# arduino_328p.net
KiCad netlist of a schematic drawn in EAGLE
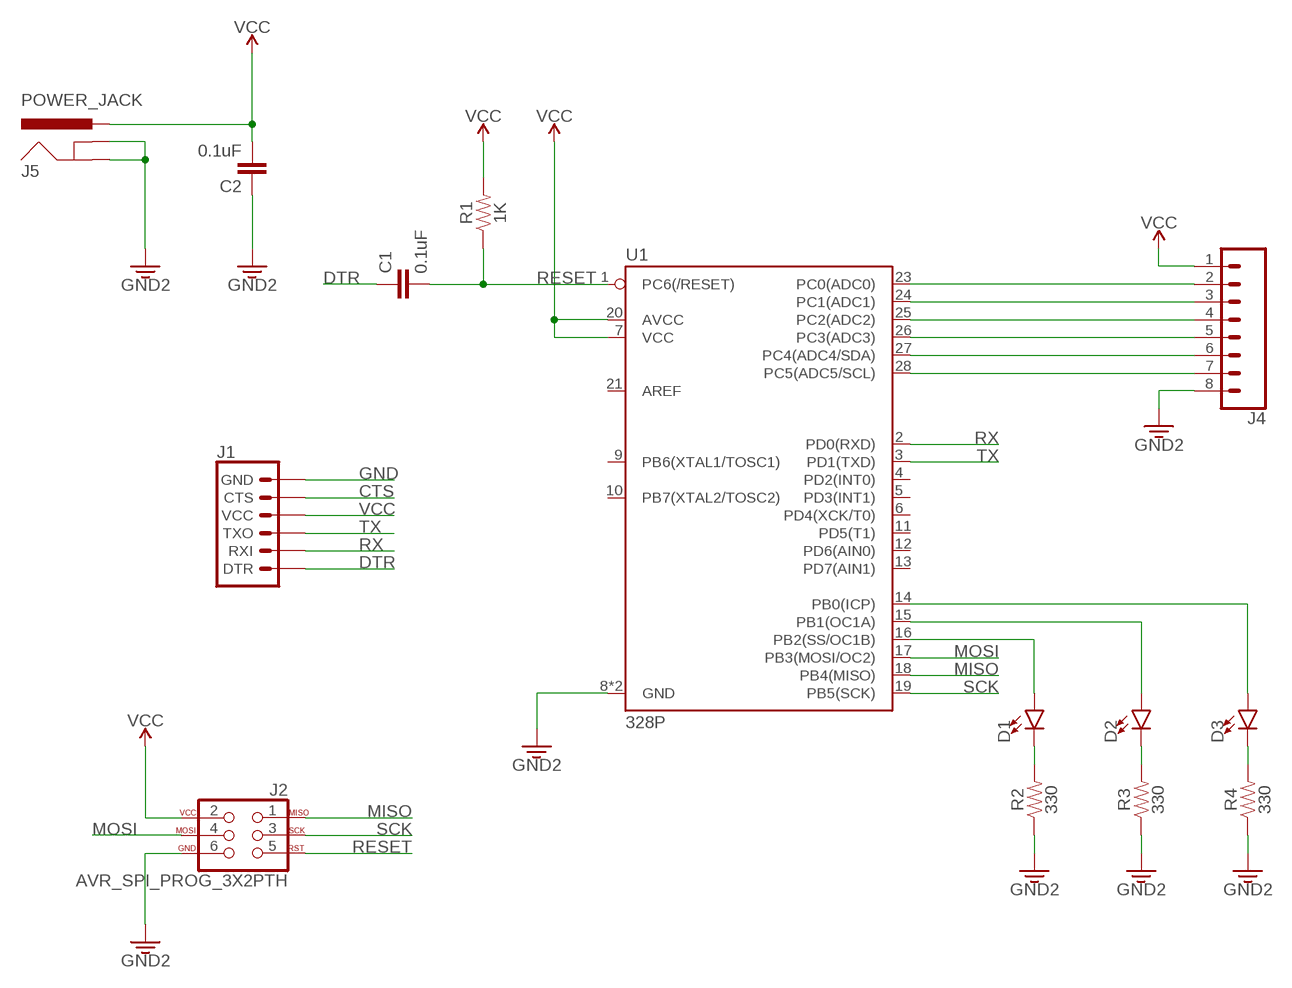
[diagram p0: schematic, sheet 1]

(export (version "E")
  (design (tool "Eeschema 10.0.6"))
  (components
    (comp (ref "C1")
      (value "0.1uF")
      (footprint "eagle-import:0402")
      (libsource (lib "eagle-import") (part "0.1UF-0402-6.3V-10%-X7R"))
    )
    (comp (ref "C2")
      (value "0.1uF")
      (footprint "eagle-import:0402")
      (libsource (lib "eagle-import") (part "0.1UF-0402-6.3V-10%-X7R"))
    )
    (comp (ref "D1")
      (value "LED1206")
      (footprint "eagle-import:LED-1206")
      (libsource (lib "eagle-import") (part "LED1206"))
    )
    (comp (ref "D2")
      (value "LED1206")
      (footprint "eagle-import:LED-1206")
      (libsource (lib "eagle-import") (part "LED1206"))
    )
    (comp (ref "D3")
      (value "LED1206")
      (footprint "eagle-import:LED-1206")
      (libsource (lib "eagle-import") (part "LED1206"))
    )
    (comp (ref "J1")
      (value "6_PIN_SERIAL_TARGETPTH-KIT")
      (footprint "eagle-import:1X06-KIT")
      (libsource (lib "eagle-import") (part "6_PIN_SERIAL_TARGETPTH-KIT"))
    )
    (comp (ref "J2")
      (value "AVR_SPI_PROG_3X2PTH")
      (footprint "eagle-import:2X3")
      (libsource (lib "eagle-import") (part "AVR_SPI_PROG_3X2PTH"))
    )
    (comp (ref "J4")
      (value "CONN_08\"")
      (footprint "eagle-import:1X08")
      (libsource (lib "eagle-import") (part "CONN_08{dblquote}"))
    )
    (comp (ref "J5")
      (value "POWER_JACK")
      (footprint "eagle-import:POWER_JACK_PTH")
      (libsource (lib "eagle-import") (part "POWER_JACK"))
    )
    (comp (ref "R1")
      (value "1K")
      (footprint "eagle-import:0805")
      (libsource (lib "eagle-import") (part "0.22OHM-0805-1/4W-1%"))
    )
    (comp (ref "R2")
      (value "330")
      (footprint "eagle-import:0805")
      (libsource (lib "eagle-import") (part "0.22OHM-0805-1/4W-1%"))
    )
    (comp (ref "R3")
      (value "330")
      (footprint "eagle-import:0805")
      (libsource (lib "eagle-import") (part "0.22OHM-0805-1/4W-1%"))
    )
    (comp (ref "R4")
      (value "330")
      (footprint "eagle-import:0805")
      (libsource (lib "eagle-import") (part "0.22OHM-0805-1/4W-1%"))
    )
    (comp (ref "U1")
      (value "328P")
      (footprint "eagle-import:DIP28")
      (libsource (lib "eagle-import") (part "ATMEGA328P_PDIP"))
    )
  )
  (nets
    (net (code "1") (name "/CTS") (class "Default")
      (node (ref "J1") (pin "5") (pinfunction "CTS_5") (pintype "passive"))
    )
    (net (code "2") (name "/DTR") (class "Default")
      (node (ref "C1") (pin "1") (pinfunction "1_1") (pintype "passive"))
      (node (ref "J1") (pin "1") (pinfunction "DTR_1") (pintype "passive"))
    )
    (net (code "3") (name "/MISO") (class "Default")
      (node (ref "J2") (pin "1") (pinfunction "1_1") (pintype "passive"))
      (node (ref "U1") (pin "18") (pinfunction "PB4(MISO)_18") (pintype "bidirectional"))
    )
    (net (code "4") (name "/MOSI") (class "Default")
      (node (ref "J2") (pin "4") (pinfunction "4_4") (pintype "passive"))
      (node (ref "U1") (pin "17") (pinfunction "PB3(MOSI/OC2)_17") (pintype "bidirectional"))
    )
    (net (code "5") (name "/RESET") (class "Default")
      (node (ref "C1") (pin "2") (pinfunction "2_2") (pintype "passive"))
      (node (ref "J2") (pin "5") (pinfunction "5_5") (pintype "passive"))
      (node (ref "R1") (pin "1") (pinfunction "1_1") (pintype "passive"))
      (node (ref "U1") (pin "1") (pinfunction "PC6(/RESET)_1") (pintype "bidirectional"))
    )
    (net (code "6") (name "/RX") (class "Default")
      (node (ref "J1") (pin "2") (pinfunction "RXI_2") (pintype "passive"))
      (node (ref "U1") (pin "2") (pinfunction "PD0(RXD)_2") (pintype "bidirectional"))
    )
    (net (code "7") (name "/SCK") (class "Default")
      (node (ref "J2") (pin "3") (pinfunction "3_3") (pintype "passive"))
      (node (ref "U1") (pin "19") (pinfunction "PB5(SCK)_19") (pintype "bidirectional"))
    )
    (net (code "8") (name "/TX") (class "Default")
      (node (ref "J1") (pin "3") (pinfunction "TXO_3") (pintype "passive"))
      (node (ref "U1") (pin "3") (pinfunction "PD1(TXD)_3") (pintype "bidirectional"))
    )
    (net (code "9") (name "GND2") (class "Default")
      (node (ref "C2") (pin "1") (pinfunction "1_1") (pintype "passive"))
      (node (ref "J1") (pin "6") (pinfunction "GND_6") (pintype "passive"))
      (node (ref "J2") (pin "6") (pinfunction "6_6") (pintype "passive"))
      (node (ref "J4") (pin "8") (pinfunction "8_8") (pintype "passive"))
      (node (ref "J5") (pin "GND") (pinfunction "GND_GND") (pintype "bidirectional"))
      (node (ref "J5") (pin "GNDBREAK") (pinfunction "GNDBREAK_GNDBREAK") (pintype "bidirectional"))
      (node (ref "R2") (pin "1") (pinfunction "1_1") (pintype "passive"))
      (node (ref "R3") (pin "1") (pinfunction "1_1") (pintype "passive"))
      (node (ref "R4") (pin "1") (pinfunction "1_1") (pintype "passive"))
      (node (ref "U1") (pin "22") (pinfunction "GND_22") (pintype "bidirectional"))
      (node (ref "U1") (pin "8") (pinfunction "GND_8") (pintype "bidirectional"))
    )
    (net (code "10") (name "Net-(D1-PadC)") (class "Default")
      (node (ref "D1") (pin "C") (pinfunction "C_C") (pintype "passive"))
      (node (ref "R2") (pin "2") (pinfunction "2_2") (pintype "passive"))
    )
    (net (code "11") (name "Net-(D2-PadC)") (class "Default")
      (node (ref "D2") (pin "C") (pinfunction "C_C") (pintype "passive"))
      (node (ref "R3") (pin "2") (pinfunction "2_2") (pintype "passive"))
    )
    (net (code "12") (name "Net-(D3-PadC)") (class "Default")
      (node (ref "D3") (pin "C") (pinfunction "C_C") (pintype "passive"))
      (node (ref "R4") (pin "2") (pinfunction "2_2") (pintype "passive"))
    )
    (net (code "13") (name "Net-(U1-PB0(ICP))") (class "Default")
      (node (ref "D3") (pin "A") (pinfunction "A_A") (pintype "passive"))
      (node (ref "U1") (pin "14") (pinfunction "PB0(ICP)_14") (pintype "bidirectional"))
    )
    (net (code "14") (name "Net-(U1-PB1(OC1A))") (class "Default")
      (node (ref "D2") (pin "A") (pinfunction "A_A") (pintype "passive"))
      (node (ref "U1") (pin "15") (pinfunction "PB1(OC1A)_15") (pintype "bidirectional"))
    )
    (net (code "15") (name "Net-(U1-PB2(SS{slash}OC1B))") (class "Default")
      (node (ref "D1") (pin "A") (pinfunction "A_A") (pintype "passive"))
      (node (ref "U1") (pin "16") (pinfunction "PB2(SS/OC1B)_16") (pintype "bidirectional"))
    )
    (net (code "16") (name "Net-(U1-PC0(ADC0))") (class "Default")
      (node (ref "J4") (pin "2") (pinfunction "2_2") (pintype "passive"))
      (node (ref "U1") (pin "23") (pinfunction "PC0(ADC0)_23") (pintype "bidirectional"))
    )
    (net (code "17") (name "Net-(U1-PC1(ADC1))") (class "Default")
      (node (ref "J4") (pin "3") (pinfunction "3_3") (pintype "passive"))
      (node (ref "U1") (pin "24") (pinfunction "PC1(ADC1)_24") (pintype "bidirectional"))
    )
    (net (code "18") (name "Net-(U1-PC2(ADC2))") (class "Default")
      (node (ref "J4") (pin "4") (pinfunction "4_4") (pintype "passive"))
      (node (ref "U1") (pin "25") (pinfunction "PC2(ADC2)_25") (pintype "bidirectional"))
    )
    (net (code "19") (name "Net-(U1-PC3(ADC3))") (class "Default")
      (node (ref "J4") (pin "5") (pinfunction "5_5") (pintype "passive"))
      (node (ref "U1") (pin "26") (pinfunction "PC3(ADC3)_26") (pintype "bidirectional"))
    )
    (net (code "20") (name "Net-(U1-PC4(ADC4{slash}SDA))") (class "Default")
      (node (ref "J4") (pin "6") (pinfunction "6_6") (pintype "passive"))
      (node (ref "U1") (pin "27") (pinfunction "PC4(ADC4/SDA)_27") (pintype "bidirectional"))
    )
    (net (code "21") (name "Net-(U1-PC5(ADC5{slash}SCL))") (class "Default")
      (node (ref "J4") (pin "7") (pinfunction "7_7") (pintype "passive"))
      (node (ref "U1") (pin "28") (pinfunction "PC5(ADC5/SCL)_28") (pintype "bidirectional"))
    )
    (net (code "22") (name "VCC") (class "Default")
      (node (ref "C2") (pin "2") (pinfunction "2_2") (pintype "passive"))
      (node (ref "J1") (pin "4") (pinfunction "VCC_4") (pintype "passive"))
      (node (ref "J2") (pin "2") (pinfunction "2_2") (pintype "passive"))
      (node (ref "J4") (pin "1") (pinfunction "1_1") (pintype "passive"))
      (node (ref "J5") (pin "PWR") (pinfunction "PWR_PWR") (pintype "bidirectional"))
      (node (ref "R1") (pin "2") (pinfunction "2_2") (pintype "passive"))
      (node (ref "U1") (pin "20") (pinfunction "AVCC_20") (pintype "bidirectional"))
      (node (ref "U1") (pin "7") (pinfunction "VCC_7") (pintype "bidirectional"))
    )
    (net (code "23") (name "unconnected-(U1-AREF-Pad21)") (class "Default")
      (node (ref "U1") (pin "21") (pinfunction "AREF_21") (pintype "bidirectional"))
    )
    (net (code "24") (name "unconnected-(U1-PB6(XTAL1{slash}TOSC1)-Pad9)") (class "Default")
      (node (ref "U1") (pin "9") (pinfunction "PB6(XTAL1/TOSC1)_9") (pintype "bidirectional"))
    )
    (net (code "25") (name "unconnected-(U1-PB7(XTAL2{slash}TOSC2)-Pad10)") (class "Default")
      (node (ref "U1") (pin "10") (pinfunction "PB7(XTAL2/TOSC2)_10") (pintype "bidirectional"))
    )
    (net (code "26") (name "unconnected-(U1-PD2(INT0)-Pad4)") (class "Default")
      (node (ref "U1") (pin "4") (pinfunction "PD2(INT0)_4") (pintype "bidirectional"))
    )
    (net (code "27") (name "unconnected-(U1-PD3(INT1)-Pad5)") (class "Default")
      (node (ref "U1") (pin "5") (pinfunction "PD3(INT1)_5") (pintype "bidirectional"))
    )
    (net (code "28") (name "unconnected-(U1-PD4(XCK{slash}T0)-Pad6)") (class "Default")
      (node (ref "U1") (pin "6") (pinfunction "PD4(XCK/T0)_6") (pintype "bidirectional"))
    )
    (net (code "29") (name "unconnected-(U1-PD5(T1)-Pad11)") (class "Default")
      (node (ref "U1") (pin "11") (pinfunction "PD5(T1)_11") (pintype "bidirectional"))
    )
    (net (code "30") (name "unconnected-(U1-PD6(AIN0)-Pad12)") (class "Default")
      (node (ref "U1") (pin "12") (pinfunction "PD6(AIN0)_12") (pintype "bidirectional"))
    )
    (net (code "31") (name "unconnected-(U1-PD7(AIN1)-Pad13)") (class "Default")
      (node (ref "U1") (pin "13") (pinfunction "PD7(AIN1)_13") (pintype "bidirectional"))
    )
  )
)
